# Teensy_Drum_Adapter.net
KiCad netlist of a schematic drawn in EAGLE
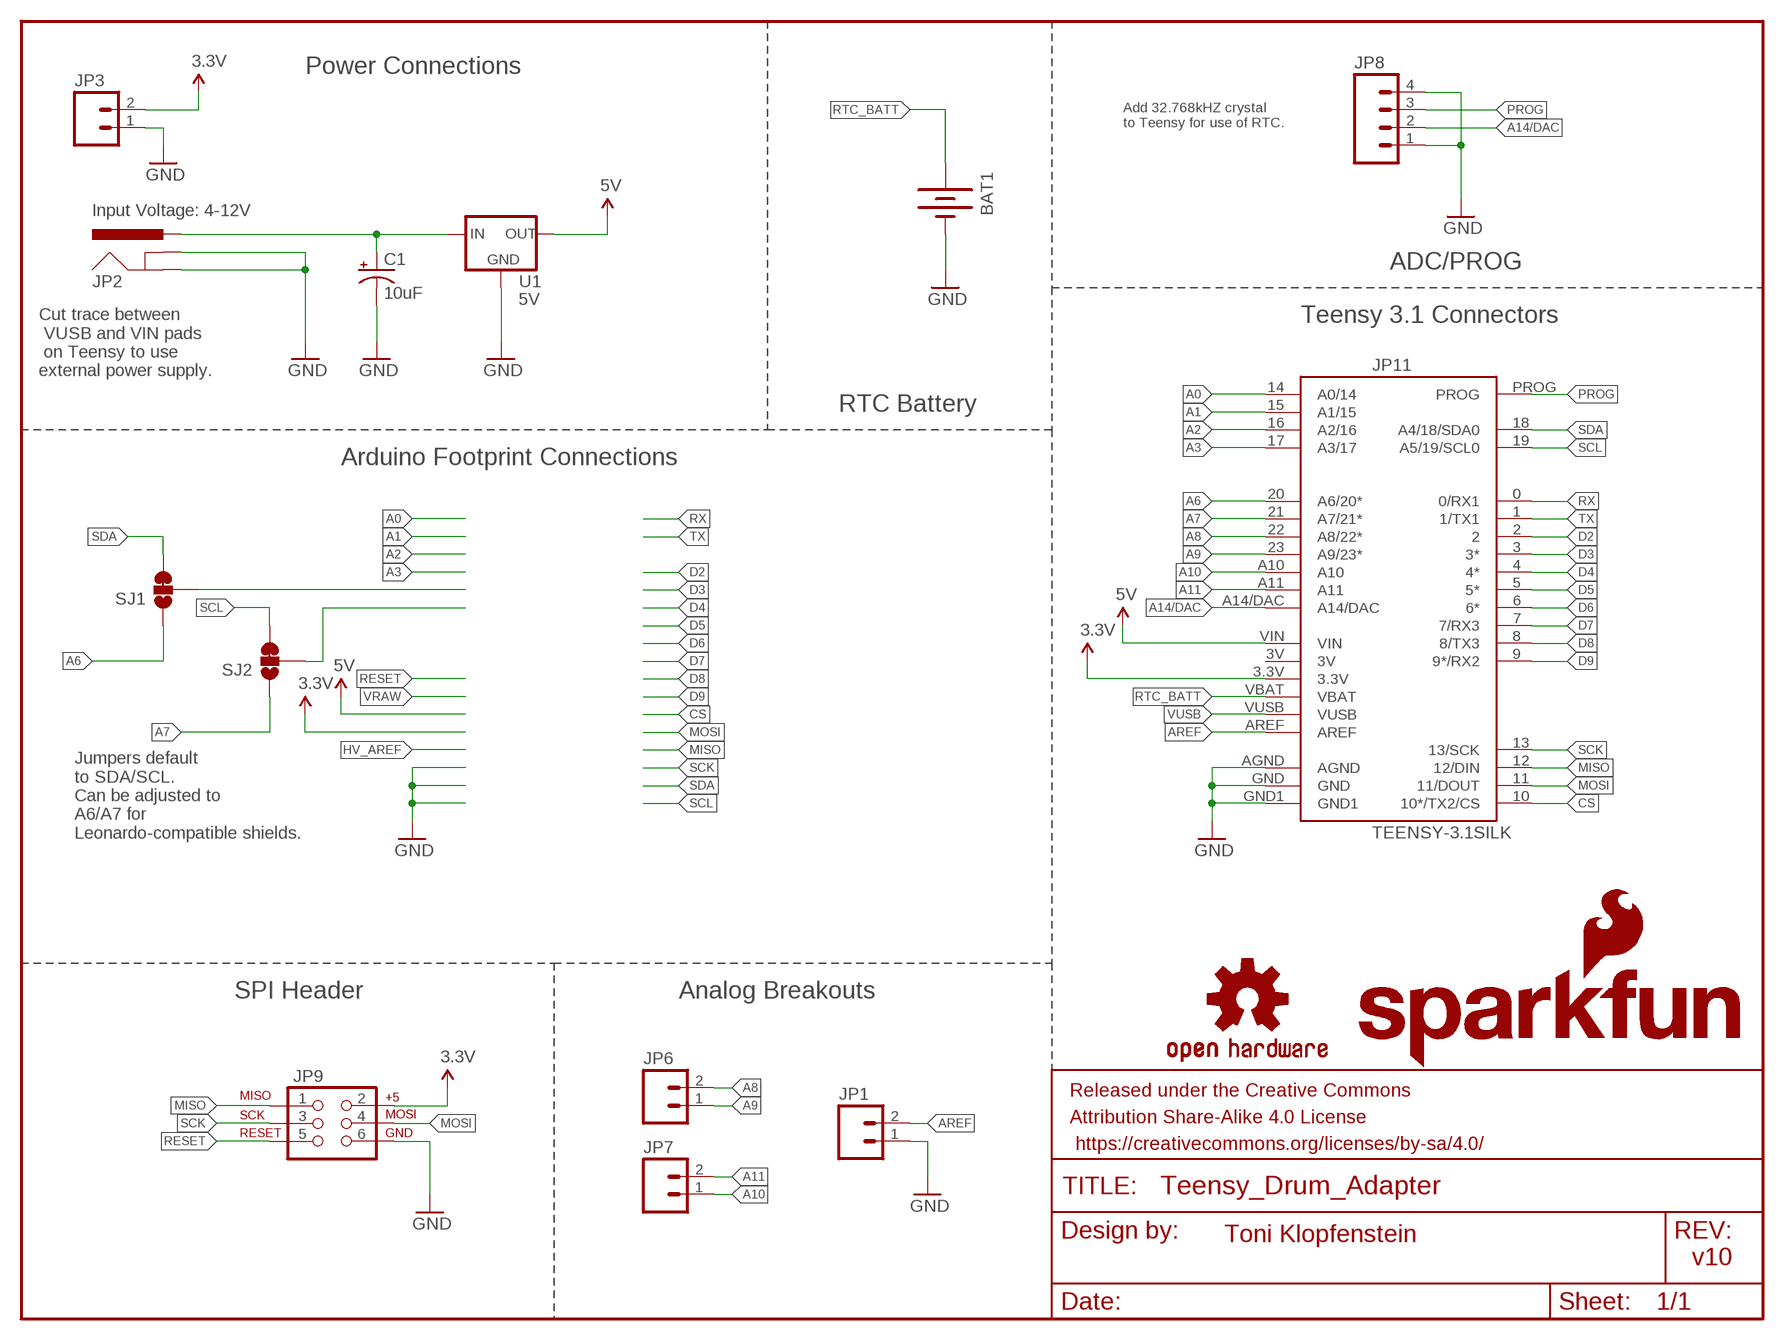
[diagram p0: schematic, sheet 1]

(export (version "E")
  (design (tool "Eeschema 10.0.6"))
  (components
    (comp (ref "BAT1")
      (value "BATTERY12PTH")
      (footprint "eagle-import:BATTCON_12MM_PTH")
      (libsource (lib "eagle-import") (part "BATTERY12PTH"))
    )
    (comp (ref "C1")
      (value "10uF")
      (footprint "eagle-import:CPOL-RADIAL-10UF-25V")
      (libsource (lib "eagle-import") (part "10UF-25V-20%(PTH)"))
    )
    (comp (ref "FRAME1")
      (value "FRAME-LETTER")
      (footprint "eagle-import:CREATIVE_COMMONS")
      (fields (field (name "DESIGNER") "Toni Klopfenstein") (field (name "VERSION") "v10"))
      (libsource (lib "eagle-import") (part "FRAME-LETTER"))
    )
    (comp (ref "JP1")
      (value "M02PTH")
      (footprint "eagle-import:1X02")
      (libsource (lib "eagle-import") (part "M02PTH"))
    )
    (comp (ref "JP2")
      (value "POWER_JACKPTH_LOCK")
      (footprint "eagle-import:POWER_JACK_PTH_LOCK")
      (libsource (lib "eagle-import") (part "POWER_JACKPTH_LOCK"))
    )
    (comp (ref "JP3")
      (value "M02JST-PTH-2")
      (footprint "eagle-import:JST-2-PTH")
      (libsource (lib "eagle-import") (part "M02JST-PTH-2"))
    )
    (comp (ref "JP6")
      (value "M02PTH")
      (footprint "eagle-import:1X02")
      (libsource (lib "eagle-import") (part "M02PTH"))
    )
    (comp (ref "JP7")
      (value "M02PTH")
      (footprint "eagle-import:1X02")
      (libsource (lib "eagle-import") (part "M02PTH"))
    )
    (comp (ref "JP8")
      (value "M04PTH")
      (footprint "eagle-import:1X04")
      (libsource (lib "eagle-import") (part "M04PTH"))
    )
    (comp (ref "JP9")
      (value "AVR_SPI_PRG_6PTH")
      (footprint "eagle-import:2X3")
      (libsource (lib "eagle-import") (part "AVR_SPI_PRG_6PTH"))
    )
    (comp (ref "JP11")
      (value "TEENSY-3.1SILK")
      (footprint "eagle-import:TEENSY-3.1")
      (libsource (lib "eagle-import") (part "TEENSY-3.1SILK"))
    )
    (comp (ref "LOGO1")
      (value "SFE_LOGO_NAME_FLAME.1_INCH")
      (footprint "eagle-import:SFE_LOGO_NAME_FLAME_.1")
      (libsource (lib "eagle-import") (part "SFE_LOGO_NAME_FLAME.1_INCH"))
    )
    (comp (ref "LOGO2")
      (value "OSHW-LOGOM")
      (footprint "eagle-import:OSHW-LOGO-M")
      (libsource (lib "eagle-import") (part "OSHW-LOGOM"))
    )
    (comp (ref "SJ1")
      (value "JUMPER-PAD-3-2OF3_NC_BY_TRACE_SMALL")
      (footprint "eagle-import:PAD-JUMPER-3-2OF3_NC_BY_TRACE_YES_SILK_FULL_BOX")
      (libsource (lib "eagle-import") (part "JUMPER-PAD-3-2OF3_NC_BY_TRACE_SMALL"))
    )
    (comp (ref "SJ2")
      (value "JUMPER-PAD-3-2OF3_NC_BY_TRACE_SMALL")
      (footprint "eagle-import:PAD-JUMPER-3-2OF3_NC_BY_TRACE_YES_SILK_FULL_BOX")
      (libsource (lib "eagle-import") (part "JUMPER-PAD-3-2OF3_NC_BY_TRACE_SMALL"))
    )
    (comp (ref "U1")
      (value "5V")
      (footprint "eagle-import:TO-220-ALT")
      (libsource (lib "eagle-import") (part "V_REG_78XX-TO-220"))
    )
  )
  (nets
    (net (code "1") (name "3.3V") (class "Default")
      (node (ref "JP11") (pin "3.3V") (pinfunction "3.3V_3.3V") (pintype "bidirectional"))
      (node (ref "JP3") (pin "2") (pinfunction "2_2") (pintype "passive"))
      (node (ref "JP9") (pin "2") (pinfunction "2_2") (pintype "passive"))
    )
    (net (code "2") (name "5V") (class "Default")
      (node (ref "JP11") (pin "VIN") (pinfunction "VIN_VIN") (pintype "bidirectional"))
      (node (ref "U1") (pin "OUT") (pinfunction "OUT_OUT") (pintype "output"))
    )
    (net (code "3") (name "A0") (class "Default")
      (node (ref "JP11") (pin "14") (pinfunction "A0/14_14") (pintype "bidirectional"))
    )
    (net (code "4") (name "A1") (class "Default")
      (node (ref "JP11") (pin "15") (pinfunction "A1/15_15") (pintype "bidirectional"))
    )
    (net (code "5") (name "A2") (class "Default")
      (node (ref "JP11") (pin "16") (pinfunction "A2/16_16") (pintype "bidirectional"))
    )
    (net (code "6") (name "A3") (class "Default")
      (node (ref "JP11") (pin "17") (pinfunction "A3/17_17") (pintype "bidirectional"))
    )
    (net (code "7") (name "A6") (class "Default")
      (node (ref "JP11") (pin "20") (pinfunction "A6/20*_20") (pintype "bidirectional"))
      (node (ref "SJ1") (pin "1") (pinfunction "1_1") (pintype "passive"))
    )
    (net (code "8") (name "A7") (class "Default")
      (node (ref "JP11") (pin "21") (pinfunction "A7/21*_21") (pintype "bidirectional"))
      (node (ref "SJ2") (pin "1") (pinfunction "1_1") (pintype "passive"))
    )
    (net (code "9") (name "A8") (class "Default")
      (node (ref "JP11") (pin "22") (pinfunction "A8/22*_22") (pintype "bidirectional"))
      (node (ref "JP6") (pin "2") (pinfunction "2_2") (pintype "passive"))
    )
    (net (code "10") (name "A9") (class "Default")
      (node (ref "JP11") (pin "23") (pinfunction "A9/23*_23") (pintype "bidirectional"))
      (node (ref "JP6") (pin "1") (pinfunction "1_1") (pintype "passive"))
    )
    (net (code "11") (name "A10") (class "Default")
      (node (ref "JP11") (pin "A10") (pinfunction "A10_A10") (pintype "bidirectional"))
      (node (ref "JP7") (pin "1") (pinfunction "1_1") (pintype "passive"))
    )
    (net (code "12") (name "A11") (class "Default")
      (node (ref "JP11") (pin "A11") (pinfunction "A11_A11") (pintype "bidirectional"))
      (node (ref "JP7") (pin "2") (pinfunction "2_2") (pintype "passive"))
    )
    (net (code "13") (name "A14{slash}DAC") (class "Default")
      (node (ref "JP11") (pin "A14/DAC") (pinfunction "A14/DAC_A14/DAC") (pintype "bidirectional"))
      (node (ref "JP8") (pin "2") (pinfunction "2_2") (pintype "passive"))
    )
    (net (code "14") (name "AREF") (class "Default")
      (node (ref "JP1") (pin "2") (pinfunction "2_2") (pintype "passive"))
      (node (ref "JP11") (pin "AREF") (pinfunction "AREF_AREF") (pintype "bidirectional"))
    )
    (net (code "15") (name "CS") (class "Default")
      (node (ref "JP11") (pin "10") (pinfunction "10*/TX2/CS_10") (pintype "bidirectional"))
    )
    (net (code "16") (name "D2") (class "Default")
      (node (ref "JP11") (pin "2") (pinfunction "2_2") (pintype "bidirectional"))
    )
    (net (code "17") (name "D3") (class "Default")
      (node (ref "JP11") (pin "3") (pinfunction "3*_3") (pintype "bidirectional"))
    )
    (net (code "18") (name "D4") (class "Default")
      (node (ref "JP11") (pin "4") (pinfunction "4*_4") (pintype "bidirectional"))
    )
    (net (code "19") (name "D5") (class "Default")
      (node (ref "JP11") (pin "5") (pinfunction "5*_5") (pintype "bidirectional"))
    )
    (net (code "20") (name "D6") (class "Default")
      (node (ref "JP11") (pin "6") (pinfunction "6*_6") (pintype "bidirectional"))
    )
    (net (code "21") (name "D7") (class "Default")
      (node (ref "JP11") (pin "7") (pinfunction "7/RX3_7") (pintype "bidirectional"))
    )
    (net (code "22") (name "D8") (class "Default")
      (node (ref "JP11") (pin "8") (pinfunction "8/TX3_8") (pintype "bidirectional"))
    )
    (net (code "23") (name "D9") (class "Default")
      (node (ref "JP11") (pin "9") (pinfunction "9*/RX2_9") (pintype "bidirectional"))
    )
    (net (code "24") (name "GND") (class "Default")
      (node (ref "BAT1") (pin "GND") (pinfunction "-_GND") (pintype "power_in"))
      (node (ref "C1") (pin "2") (pinfunction "-_2") (pintype "passive"))
      (node (ref "JP1") (pin "1") (pinfunction "1_1") (pintype "passive"))
      (node (ref "JP11") (pin "AGND") (pinfunction "AGND_AGND") (pintype "bidirectional"))
      (node (ref "JP11") (pin "GND") (pinfunction "GND_GND") (pintype "bidirectional"))
      (node (ref "JP11") (pin "GND1") (pinfunction "GND1_GND1") (pintype "bidirectional"))
      (node (ref "JP2") (pin "GND") (pinfunction "GND_GND") (pintype "bidirectional"))
      (node (ref "JP2") (pin "GNDBREAK") (pinfunction "GNDBREAK_GNDBREAK") (pintype "bidirectional"))
      (node (ref "JP3") (pin "1") (pinfunction "1_1") (pintype "passive"))
      (node (ref "JP8") (pin "1") (pinfunction "1_1") (pintype "passive"))
      (node (ref "JP8") (pin "4") (pinfunction "4_4") (pintype "passive"))
      (node (ref "JP9") (pin "6") (pinfunction "6_6") (pintype "passive"))
      (node (ref "U1") (pin "GND") (pinfunction "GND_GND") (pintype "input"))
    )
    (net (code "26") (name "MISO") (class "Default")
      (node (ref "JP11") (pin "12") (pinfunction "12/DIN_12") (pintype "bidirectional"))
      (node (ref "JP9") (pin "1") (pinfunction "1_1") (pintype "passive"))
    )
    (net (code "27") (name "MOSI") (class "Default")
      (node (ref "JP11") (pin "11") (pinfunction "11/DOUT_11") (pintype "bidirectional"))
      (node (ref "JP9") (pin "4") (pinfunction "4_4") (pintype "passive"))
    )
    (net (code "28") (name "PROG") (class "Default")
      (node (ref "JP11") (pin "PROG") (pinfunction "PROG_PROG") (pintype "bidirectional"))
      (node (ref "JP8") (pin "3") (pinfunction "3_3") (pintype "passive"))
    )
    (net (code "29") (name "RESET") (class "Default")
      (node (ref "JP9") (pin "5") (pinfunction "5_5") (pintype "passive"))
    )
    (net (code "30") (name "RTC_BATT") (class "Default")
      (node (ref "BAT1") (pin "VCC@1") (pinfunction "+_VCC@1") (pintype "power_in"))
      (node (ref "JP11") (pin "VBAT") (pinfunction "VBAT_VBAT") (pintype "bidirectional"))
    )
    (net (code "31") (name "RX") (class "Default")
      (node (ref "JP11") (pin "0") (pinfunction "0/RX1_0") (pintype "bidirectional"))
    )
    (net (code "32") (name "SCK") (class "Default")
      (node (ref "JP11") (pin "13") (pinfunction "13/SCK_13") (pintype "bidirectional"))
      (node (ref "JP9") (pin "3") (pinfunction "3_3") (pintype "passive"))
    )
    (net (code "33") (name "SCL") (class "Default")
      (node (ref "JP11") (pin "19") (pinfunction "A5/19/SCL0_19") (pintype "bidirectional"))
      (node (ref "SJ2") (pin "3") (pinfunction "3_3") (pintype "passive"))
    )
    (net (code "34") (name "SDA") (class "Default")
      (node (ref "JP11") (pin "18") (pinfunction "A4/18/SDA0_18") (pintype "bidirectional"))
      (node (ref "SJ1") (pin "3") (pinfunction "3_3") (pintype "passive"))
    )
    (net (code "35") (name "TX") (class "Default")
      (node (ref "JP11") (pin "1") (pinfunction "1/TX1_1") (pintype "bidirectional"))
    )
    (net (code "36") (name "VRAW") (class "Default")
      (node (ref "C1") (pin "1") (pinfunction "+_1") (pintype "passive"))
      (node (ref "JP2") (pin "PWR") (pinfunction "PWR_PWR") (pintype "bidirectional"))
      (node (ref "U1") (pin "IN") (pinfunction "IN_IN") (pintype "input"))
    )
    (net (code "37") (name "VUSB") (class "Default")
      (node (ref "JP11") (pin "VUSB") (pinfunction "VUSB_VUSB") (pintype "bidirectional"))
    )
    (net (code "38") (name "unconnected-(JP11-Pad3V)") (class "Default")
      (node (ref "JP11") (pin "3V") (pinfunction "3V_3V") (pintype "bidirectional"))
    )
    (net (code "39") (name "unconnected-(SJ1-Pad2)") (class "Default")
      (node (ref "SJ1") (pin "2") (pinfunction "2_2") (pintype "passive"))
    )
    (net (code "40") (name "unconnected-(SJ2-Pad2)") (class "Default")
      (node (ref "SJ2") (pin "2") (pinfunction "2_2") (pintype "passive"))
    )
  )
)
